# PGA-103_LNA.net
KiCad netlist of a schematic drawn in EAGLE
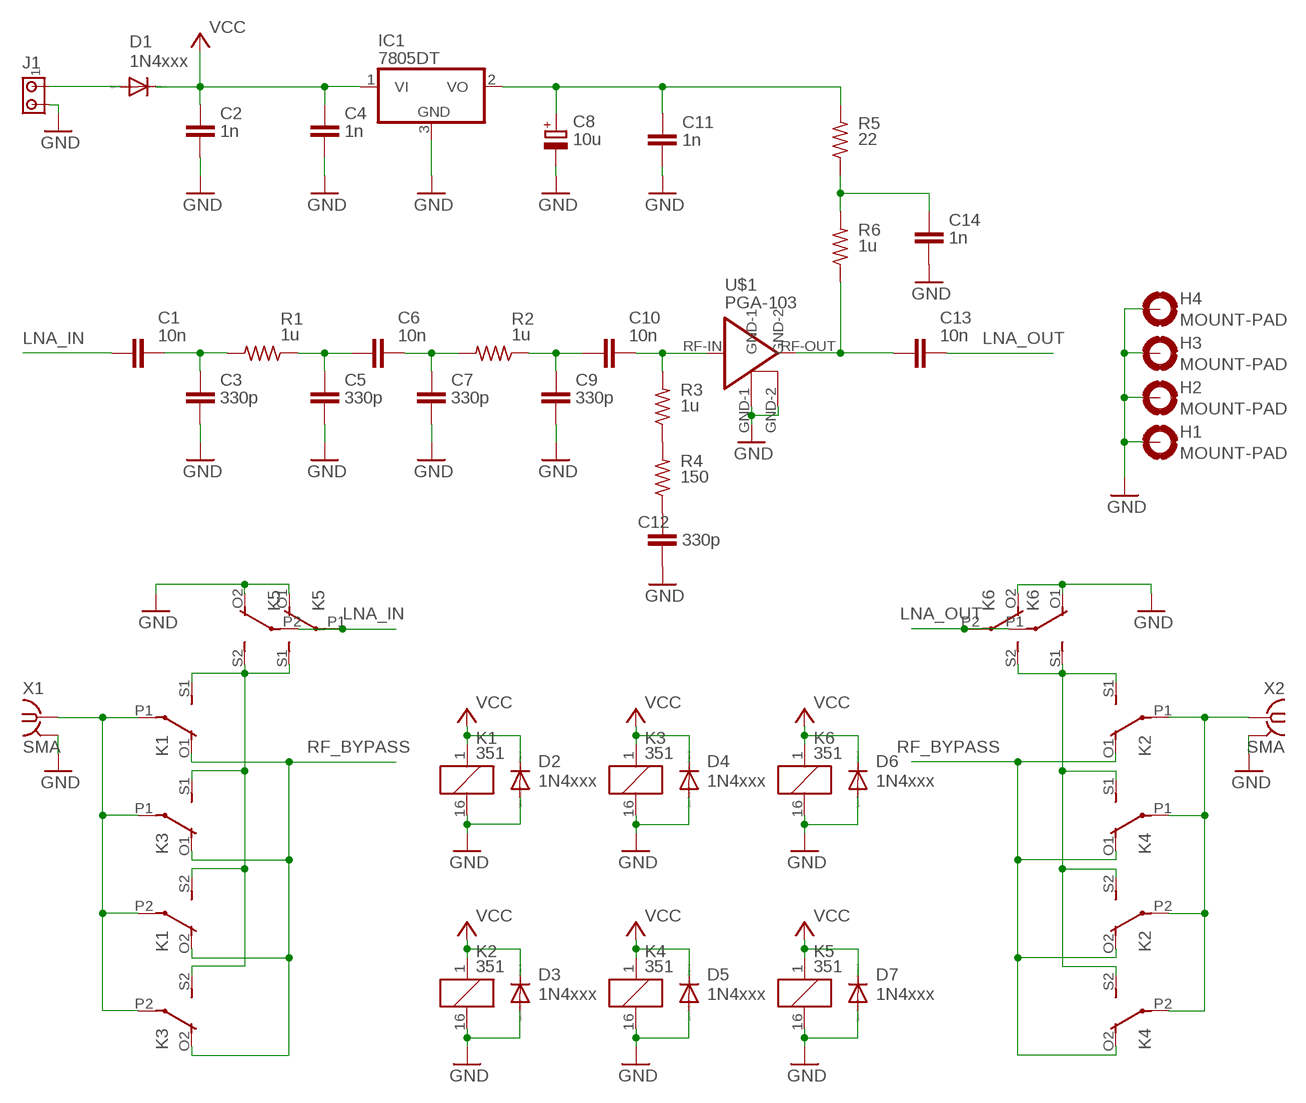
[diagram p0: schematic, sheet 1]

(export (version "E")
  (design (tool "Eeschema 10.0.6"))
  (components
    (comp (ref "C1")
      (value "10n")
      (footprint "eagle-import:C1206")
      (libsource (lib "eagle-import") (part "C-EUC1206"))
    )
    (comp (ref "C2")
      (value "1n")
      (footprint "eagle-import:C1206")
      (libsource (lib "eagle-import") (part "C-EUC1206"))
    )
    (comp (ref "C3")
      (value "330p")
      (footprint "eagle-import:C1206")
      (libsource (lib "eagle-import") (part "C-EUC1206"))
    )
    (comp (ref "C4")
      (value "1n")
      (footprint "eagle-import:C1206")
      (libsource (lib "eagle-import") (part "C-EUC1206"))
    )
    (comp (ref "C5")
      (value "330p")
      (footprint "eagle-import:C1206")
      (libsource (lib "eagle-import") (part "C-EUC1206"))
    )
    (comp (ref "C6")
      (value "10n")
      (footprint "eagle-import:C1206")
      (libsource (lib "eagle-import") (part "C-EUC1206"))
    )
    (comp (ref "C7")
      (value "330p")
      (footprint "eagle-import:C1206")
      (libsource (lib "eagle-import") (part "C-EUC1206"))
    )
    (comp (ref "C8")
      (value "10u")
      (footprint "eagle-import:CT6032")
      (libsource (lib "eagle-import") (part "CPOL-EUCT6032"))
    )
    (comp (ref "C9")
      (value "330p")
      (footprint "eagle-import:C1206")
      (libsource (lib "eagle-import") (part "C-EUC1206"))
    )
    (comp (ref "C10")
      (value "10n")
      (footprint "eagle-import:C1206")
      (libsource (lib "eagle-import") (part "C-EUC1206"))
    )
    (comp (ref "C11")
      (value "1n")
      (footprint "eagle-import:C1206")
      (libsource (lib "eagle-import") (part "C-EUC1206"))
    )
    (comp (ref "C12")
      (value "330p")
      (footprint "eagle-import:C1206")
      (libsource (lib "eagle-import") (part "C-EUC1206"))
    )
    (comp (ref "C13")
      (value "10n")
      (footprint "eagle-import:C1206")
      (libsource (lib "eagle-import") (part "C-EUC1206"))
    )
    (comp (ref "C14")
      (value "1n")
      (footprint "eagle-import:C1206")
      (libsource (lib "eagle-import") (part "C-EUC1206"))
    )
    (comp (ref "D1")
      (value "1N4xxx")
      (footprint "eagle-import:DO35-7")
      (libsource (lib "eagle-import") (part "1N4148DO35-7"))
    )
    (comp (ref "D2")
      (value "1N4xxx")
      (footprint "eagle-import:DO35-7")
      (libsource (lib "eagle-import") (part "1N4148DO35-7"))
    )
    (comp (ref "D3")
      (value "1N4xxx")
      (footprint "eagle-import:DO35-7")
      (libsource (lib "eagle-import") (part "1N4148DO35-7"))
    )
    (comp (ref "D4")
      (value "1N4xxx")
      (footprint "eagle-import:DO35-7")
      (libsource (lib "eagle-import") (part "1N4148DO35-7"))
    )
    (comp (ref "D5")
      (value "1N4xxx")
      (footprint "eagle-import:DO35-7")
      (libsource (lib "eagle-import") (part "1N4148DO35-7"))
    )
    (comp (ref "D6")
      (value "1N4xxx")
      (footprint "eagle-import:DO35-7")
      (libsource (lib "eagle-import") (part "1N4148DO35-7"))
    )
    (comp (ref "D7")
      (value "1N4xxx")
      (footprint "eagle-import:DO35-7")
      (libsource (lib "eagle-import") (part "1N4148DO35-7"))
    )
    (comp (ref "H1")
      (value "MOUNT-PAD")
      (footprint "eagle-import:2,8-PAD")
      (libsource (lib "eagle-import") (part "MOUNT-PAD-ROUND2.8"))
    )
    (comp (ref "H2")
      (value "MOUNT-PAD")
      (footprint "eagle-import:2,8-PAD")
      (libsource (lib "eagle-import") (part "MOUNT-PAD-ROUND2.8"))
    )
    (comp (ref "H3")
      (value "MOUNT-PAD")
      (footprint "eagle-import:2,8-PAD")
      (libsource (lib "eagle-import") (part "MOUNT-PAD-ROUND2.8"))
    )
    (comp (ref "H4")
      (value "MOUNT-PAD")
      (footprint "eagle-import:2,8-PAD")
      (libsource (lib "eagle-import") (part "MOUNT-PAD-ROUND2.8"))
    )
    (comp (ref "IC1")
      (value "7805DT")
      (footprint "eagle-import:TO252")
      (libsource (lib "eagle-import") (part "78DT05"))
    )
    (comp (ref "J1")
      (value "MTA02-156")
      (footprint "eagle-import:1X2MTA")
      (libsource (lib "eagle-import") (part "MTA02-156"))
    )
    (comp (ref "K1")
      (value "351")
      (footprint "eagle-import:351")
      (libsource (lib "eagle-import") (part "351"))
    )
    (comp (ref "K2")
      (value "351")
      (footprint "eagle-import:351")
      (libsource (lib "eagle-import") (part "351"))
    )
    (comp (ref "K3")
      (value "351")
      (footprint "eagle-import:351")
      (libsource (lib "eagle-import") (part "351"))
    )
    (comp (ref "K4")
      (value "351")
      (footprint "eagle-import:351")
      (libsource (lib "eagle-import") (part "351"))
    )
    (comp (ref "K5")
      (value "351")
      (footprint "eagle-import:351")
      (libsource (lib "eagle-import") (part "351"))
    )
    (comp (ref "K6")
      (value "351")
      (footprint "eagle-import:351")
      (libsource (lib "eagle-import") (part "351"))
    )
    (comp (ref "R1")
      (value "1u")
      (footprint "eagle-import:M1206")
      (libsource (lib "eagle-import") (part "R-US_M1206"))
    )
    (comp (ref "R2")
      (value "1u")
      (footprint "eagle-import:M1206")
      (libsource (lib "eagle-import") (part "R-US_M1206"))
    )
    (comp (ref "R3")
      (value "1u")
      (footprint "eagle-import:M1206")
      (libsource (lib "eagle-import") (part "R-US_M1206"))
    )
    (comp (ref "R4")
      (value "150")
      (footprint "eagle-import:M1206")
      (libsource (lib "eagle-import") (part "R-US_M1206"))
    )
    (comp (ref "R5")
      (value "22")
      (footprint "eagle-import:M1206")
      (libsource (lib "eagle-import") (part "R-US_M1206"))
    )
    (comp (ref "R6")
      (value "1u")
      (footprint "eagle-import:M1206")
      (libsource (lib "eagle-import") (part "R-US_M1206"))
    )
    (comp (ref "U$1")
      (value "PGA-103")
      (footprint "eagle-import:DF782")
      (libsource (lib "eagle-import") (part "PGA-103"))
    )
    (comp (ref "X1")
      (value "SMA")
      (footprint "eagle-import:J502-ND-142-0701-851_861")
      (fields (field (name "MF") "JOHNSON COMPONENTS") (field (name "MPN") "142-0701-851"))
      (libsource (lib "eagle-import") (part "SMA-142-0701-851/861"))
    )
    (comp (ref "X2")
      (value "SMA")
      (footprint "eagle-import:J502-ND-142-0701-851_861")
      (fields (field (name "MF") "JOHNSON COMPONENTS") (field (name "MPN") "142-0701-851"))
      (libsource (lib "eagle-import") (part "SMA-142-0701-851/861"))
    )
  )
  (nets
    (net (code "1") (name "/LNA_IN") (class "Default")
      (node (ref "C1") (pin "1") (pinfunction "1_1") (pintype "passive"))
      (node (ref "K5") (pin "P1") (pinfunction "P_P1") (pintype "passive"))
      (node (ref "K5") (pin "P2") (pinfunction "P_P2") (pintype "passive"))
    )
    (net (code "2") (name "/LNA_OUT") (class "Default")
      (node (ref "C13") (pin "2") (pinfunction "2_2") (pintype "passive"))
      (node (ref "K6") (pin "P1") (pinfunction "P_P1") (pintype "passive"))
      (node (ref "K6") (pin "P2") (pinfunction "P_P2") (pintype "passive"))
    )
    (net (code "3") (name "/RF_BYPASS") (class "Default")
      (node (ref "K1") (pin "O1") (pinfunction "O_O1") (pintype "passive"))
      (node (ref "K1") (pin "O2") (pinfunction "O_O2") (pintype "passive"))
      (node (ref "K2") (pin "O1") (pinfunction "O_O1") (pintype "passive"))
      (node (ref "K2") (pin "O2") (pinfunction "O_O2") (pintype "passive"))
      (node (ref "K3") (pin "O1") (pinfunction "O_O1") (pintype "passive"))
      (node (ref "K3") (pin "O2") (pinfunction "O_O2") (pintype "passive"))
      (node (ref "K4") (pin "O1") (pinfunction "O_O1") (pintype "passive"))
      (node (ref "K4") (pin "O2") (pinfunction "O_O2") (pintype "passive"))
    )
    (net (code "4") (name "GND") (class "Default")
      (node (ref "C11") (pin "2") (pinfunction "2_2") (pintype "passive"))
      (node (ref "C12") (pin "1") (pinfunction "1_1") (pintype "passive"))
      (node (ref "C14") (pin "1") (pinfunction "1_1") (pintype "passive"))
      (node (ref "C2") (pin "2") (pinfunction "2_2") (pintype "passive"))
      (node (ref "C3") (pin "1") (pinfunction "1_1") (pintype "passive"))
      (node (ref "C4") (pin "2") (pinfunction "2_2") (pintype "passive"))
      (node (ref "C5") (pin "1") (pinfunction "1_1") (pintype "passive"))
      (node (ref "C7") (pin "1") (pinfunction "1_1") (pintype "passive"))
      (node (ref "C8") (pin "-") (pinfunction "-_-") (pintype "passive"))
      (node (ref "C9") (pin "1") (pinfunction "1_1") (pintype "passive"))
      (node (ref "D2") (pin "A") (pinfunction "A_A") (pintype "passive"))
      (node (ref "D3") (pin "A") (pinfunction "A_A") (pintype "passive"))
      (node (ref "D4") (pin "A") (pinfunction "A_A") (pintype "passive"))
      (node (ref "D5") (pin "A") (pinfunction "A_A") (pintype "passive"))
      (node (ref "D6") (pin "A") (pinfunction "A_A") (pintype "passive"))
      (node (ref "D7") (pin "A") (pinfunction "A_A") (pintype "passive"))
      (node (ref "H1") (pin "B2,8") (pinfunction "MOUNT_B2,8") (pintype "passive"))
      (node (ref "H2") (pin "B2,8") (pinfunction "MOUNT_B2,8") (pintype "passive"))
      (node (ref "H3") (pin "B2,8") (pinfunction "MOUNT_B2,8") (pintype "passive"))
      (node (ref "H4") (pin "B2,8") (pinfunction "MOUNT_B2,8") (pintype "passive"))
      (node (ref "IC1") (pin "3") (pinfunction "GND_3") (pintype "passive"))
      (node (ref "J1") (pin "2") (pinfunction "2_2") (pintype "passive"))
      (node (ref "K1") (pin "16") (pinfunction "2_16") (pintype "passive"))
      (node (ref "K2") (pin "16") (pinfunction "2_16") (pintype "passive"))
      (node (ref "K3") (pin "16") (pinfunction "2_16") (pintype "passive"))
      (node (ref "K4") (pin "16") (pinfunction "2_16") (pintype "passive"))
      (node (ref "K5") (pin "16") (pinfunction "2_16") (pintype "passive"))
      (node (ref "K5") (pin "O1") (pinfunction "O_O1") (pintype "passive"))
      (node (ref "K5") (pin "O2") (pinfunction "O_O2") (pintype "passive"))
      (node (ref "K6") (pin "16") (pinfunction "2_16") (pintype "passive"))
      (node (ref "K6") (pin "O1") (pinfunction "O_O1") (pintype "passive"))
      (node (ref "K6") (pin "O2") (pinfunction "O_O2") (pintype "passive"))
      (node (ref "U$1") (pin "GND-1") (pinfunction "GND-1_GND-1") (pintype "power_in"))
      (node (ref "U$1") (pin "GND-2") (pinfunction "GND-2_GND-2") (pintype "power_in"))
      (node (ref "X1") (pin "G@1") (pinfunction "2_G@1") (pintype "passive"))
      (node (ref "X1") (pin "G@2") (pinfunction "2_G@2") (pintype "passive"))
      (node (ref "X1") (pin "G@3") (pinfunction "2_G@3") (pintype "passive"))
      (node (ref "X1") (pin "G@4") (pinfunction "2_G@4") (pintype "passive"))
      (node (ref "X2") (pin "G@1") (pinfunction "2_G@1") (pintype "passive"))
      (node (ref "X2") (pin "G@2") (pinfunction "2_G@2") (pintype "passive"))
      (node (ref "X2") (pin "G@3") (pinfunction "2_G@3") (pintype "passive"))
      (node (ref "X2") (pin "G@4") (pinfunction "2_G@4") (pintype "passive"))
    )
    (net (code "5") (name "Net-(C1-Pad2)") (class "Default")
      (node (ref "C1") (pin "2") (pinfunction "2_2") (pintype "passive"))
      (node (ref "C3") (pin "2") (pinfunction "2_2") (pintype "passive"))
      (node (ref "R1") (pin "2") (pinfunction "2_2") (pintype "passive"))
    )
    (net (code "6") (name "Net-(C5-Pad2)") (class "Default")
      (node (ref "C5") (pin "2") (pinfunction "2_2") (pintype "passive"))
      (node (ref "C6") (pin "1") (pinfunction "1_1") (pintype "passive"))
      (node (ref "R1") (pin "1") (pinfunction "1_1") (pintype "passive"))
    )
    (net (code "7") (name "Net-(C6-Pad2)") (class "Default")
      (node (ref "C6") (pin "2") (pinfunction "2_2") (pintype "passive"))
      (node (ref "C7") (pin "2") (pinfunction "2_2") (pintype "passive"))
      (node (ref "R2") (pin "2") (pinfunction "2_2") (pintype "passive"))
    )
    (net (code "8") (name "Net-(C10-Pad1)") (class "Default")
      (node (ref "C10") (pin "1") (pinfunction "1_1") (pintype "passive"))
      (node (ref "C9") (pin "2") (pinfunction "2_2") (pintype "passive"))
      (node (ref "R2") (pin "1") (pinfunction "1_1") (pintype "passive"))
    )
    (net (code "9") (name "Net-(C10-Pad2)") (class "Default")
      (node (ref "C10") (pin "2") (pinfunction "2_2") (pintype "passive"))
      (node (ref "R3") (pin "2") (pinfunction "2_2") (pintype "passive"))
      (node (ref "U$1") (pin "RF-IN") (pinfunction "RF-IN_RF-IN") (pintype "input"))
    )
    (net (code "10") (name "Net-(C12-Pad2)") (class "Default")
      (node (ref "C12") (pin "2") (pinfunction "2_2") (pintype "passive"))
      (node (ref "R4") (pin "1") (pinfunction "1_1") (pintype "passive"))
    )
    (net (code "11") (name "Net-(C13-Pad1)") (class "Default")
      (node (ref "C13") (pin "1") (pinfunction "1_1") (pintype "passive"))
      (node (ref "R6") (pin "1") (pinfunction "1_1") (pintype "passive"))
      (node (ref "U$1") (pin "RF-OUT") (pinfunction "RF-OUT_RF-OUT") (pintype "output"))
    )
    (net (code "12") (name "Net-(C14-Pad2)") (class "Default")
      (node (ref "C14") (pin "2") (pinfunction "2_2") (pintype "passive"))
      (node (ref "R5") (pin "1") (pinfunction "1_1") (pintype "passive"))
      (node (ref "R6") (pin "2") (pinfunction "2_2") (pintype "passive"))
    )
    (net (code "13") (name "Net-(D1-PadA)") (class "Default")
      (node (ref "D1") (pin "A") (pinfunction "A_A") (pintype "passive"))
      (node (ref "J1") (pin "1") (pinfunction "1_1") (pintype "passive"))
    )
    (net (code "14") (name "Net-(IC1-VO)") (class "Default")
      (node (ref "C11") (pin "1") (pinfunction "1_1") (pintype "passive"))
      (node (ref "C8") (pin "+") (pinfunction "+_+") (pintype "passive"))
      (node (ref "IC1") (pin "2") (pinfunction "VO_2") (pintype "passive"))
      (node (ref "R5") (pin "2") (pinfunction "2_2") (pintype "passive"))
    )
    (net (code "15") (name "Net-(K1B-P)") (class "Default")
      (node (ref "K1") (pin "P1") (pinfunction "P_P1") (pintype "passive"))
      (node (ref "K1") (pin "P2") (pinfunction "P_P2") (pintype "passive"))
      (node (ref "K3") (pin "P1") (pinfunction "P_P1") (pintype "passive"))
      (node (ref "K3") (pin "P2") (pinfunction "P_P2") (pintype "passive"))
      (node (ref "X1") (pin "1") (pinfunction "1_1") (pintype "passive"))
    )
    (net (code "16") (name "Net-(K1B-S)") (class "Default")
      (node (ref "K1") (pin "S1") (pinfunction "S_S1") (pintype "passive"))
      (node (ref "K1") (pin "S2") (pinfunction "S_S2") (pintype "passive"))
      (node (ref "K3") (pin "S1") (pinfunction "S_S1") (pintype "passive"))
      (node (ref "K3") (pin "S2") (pinfunction "S_S2") (pintype "passive"))
      (node (ref "K5") (pin "S1") (pinfunction "S_S1") (pintype "passive"))
      (node (ref "K5") (pin "S2") (pinfunction "S_S2") (pintype "passive"))
    )
    (net (code "17") (name "Net-(K2B-P)") (class "Default")
      (node (ref "K2") (pin "P1") (pinfunction "P_P1") (pintype "passive"))
      (node (ref "K2") (pin "P2") (pinfunction "P_P2") (pintype "passive"))
      (node (ref "K4") (pin "P1") (pinfunction "P_P1") (pintype "passive"))
      (node (ref "K4") (pin "P2") (pinfunction "P_P2") (pintype "passive"))
      (node (ref "X2") (pin "1") (pinfunction "1_1") (pintype "passive"))
    )
    (net (code "18") (name "Net-(K2B-S)") (class "Default")
      (node (ref "K2") (pin "S1") (pinfunction "S_S1") (pintype "passive"))
      (node (ref "K2") (pin "S2") (pinfunction "S_S2") (pintype "passive"))
      (node (ref "K4") (pin "S1") (pinfunction "S_S1") (pintype "passive"))
      (node (ref "K4") (pin "S2") (pinfunction "S_S2") (pintype "passive"))
      (node (ref "K6") (pin "S1") (pinfunction "S_S1") (pintype "passive"))
      (node (ref "K6") (pin "S2") (pinfunction "S_S2") (pintype "passive"))
    )
    (net (code "19") (name "Net-(R3-Pad1)") (class "Default")
      (node (ref "R3") (pin "1") (pinfunction "1_1") (pintype "passive"))
      (node (ref "R4") (pin "2") (pinfunction "2_2") (pintype "passive"))
    )
    (net (code "20") (name "VCC") (class "Default")
      (node (ref "C2") (pin "1") (pinfunction "1_1") (pintype "passive"))
      (node (ref "C4") (pin "1") (pinfunction "1_1") (pintype "passive"))
      (node (ref "D1") (pin "C") (pinfunction "C_C") (pintype "passive"))
      (node (ref "D2") (pin "C") (pinfunction "C_C") (pintype "passive"))
      (node (ref "D3") (pin "C") (pinfunction "C_C") (pintype "passive"))
      (node (ref "D4") (pin "C") (pinfunction "C_C") (pintype "passive"))
      (node (ref "D5") (pin "C") (pinfunction "C_C") (pintype "passive"))
      (node (ref "D6") (pin "C") (pinfunction "C_C") (pintype "passive"))
      (node (ref "D7") (pin "C") (pinfunction "C_C") (pintype "passive"))
      (node (ref "IC1") (pin "1") (pinfunction "VI_1") (pintype "input"))
      (node (ref "K1") (pin "1") (pinfunction "1_1") (pintype "passive"))
      (node (ref "K2") (pin "1") (pinfunction "1_1") (pintype "passive"))
      (node (ref "K3") (pin "1") (pinfunction "1_1") (pintype "passive"))
      (node (ref "K4") (pin "1") (pinfunction "1_1") (pintype "passive"))
      (node (ref "K5") (pin "1") (pinfunction "1_1") (pintype "passive"))
      (node (ref "K6") (pin "1") (pinfunction "1_1") (pintype "passive"))
    )
  )
)
